# led_daughter.net
KiCad netlist of a schematic drawn in EAGLE
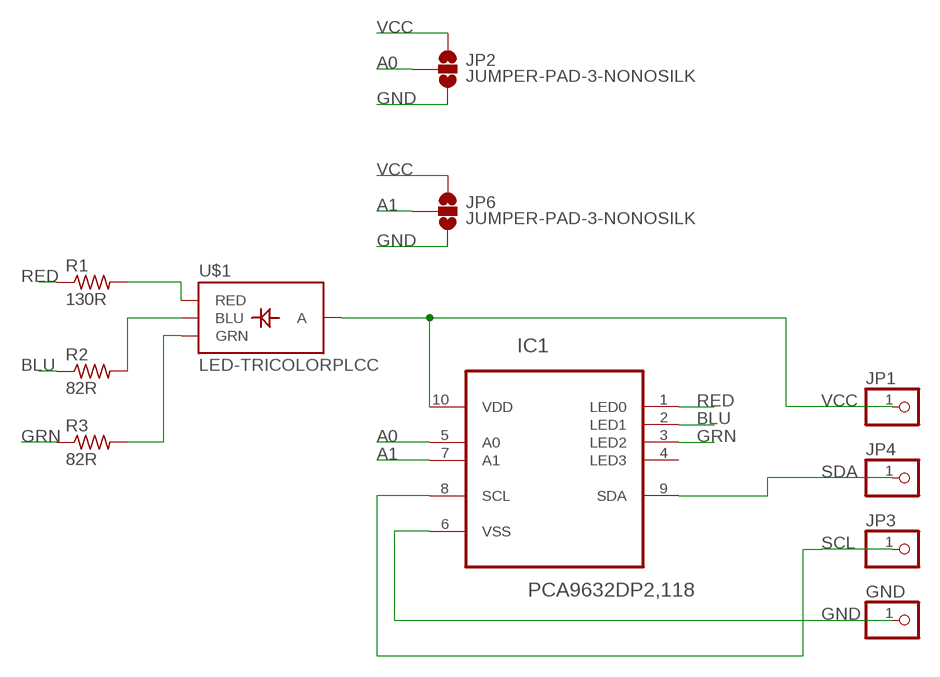
[diagram p0: schematic, sheet 1]

(export (version "E")
  (design (tool "Eeschema 10.0.6"))
  (components
    (comp (ref "GND")
      (value "PINHD-1X1CB")
      (footprint "eagle-import:1X01-CLEANBIG")
      (libsource (lib "eagle-import") (part "PINHD-1X1CB"))
    )
    (comp (ref "IC1")
      (value "PCA9632DP2,118")
      (footprint "eagle-import:SOP50P490X110-10N")
      (libsource (lib "eagle-import") (part "PCA9632DP2,118"))
    )
    (comp (ref "JP1")
      (value "PINHD-1X1CB")
      (footprint "eagle-import:1X01-CLEANBIG")
      (libsource (lib "eagle-import") (part "PINHD-1X1CB"))
    )
    (comp (ref "JP2")
      (value "JUMPER-PAD-3-NONOSILK")
      (footprint "eagle-import:PAD-JUMPER-3-NO_NO_SILK")
      (libsource (lib "eagle-import") (part "JUMPER-PAD-3-NONOSILK"))
    )
    (comp (ref "JP3")
      (value "PINHD-1X1CB")
      (footprint "eagle-import:1X01-CLEANBIG")
      (libsource (lib "eagle-import") (part "PINHD-1X1CB"))
    )
    (comp (ref "JP4")
      (value "PINHD-1X1CB")
      (footprint "eagle-import:1X01-CLEANBIG")
      (libsource (lib "eagle-import") (part "PINHD-1X1CB"))
    )
    (comp (ref "JP6")
      (value "JUMPER-PAD-3-NONOSILK")
      (footprint "eagle-import:PAD-JUMPER-3-NO_NO_SILK")
      (libsource (lib "eagle-import") (part "JUMPER-PAD-3-NONOSILK"))
    )
    (comp (ref "R1")
      (value "130R")
      (footprint "eagle-import:R0603")
      (libsource (lib "eagle-import") (part "R-US_R0603"))
    )
    (comp (ref "R2")
      (value "82R")
      (footprint "eagle-import:R0603")
      (libsource (lib "eagle-import") (part "R-US_R0603"))
    )
    (comp (ref "R3")
      (value "82R")
      (footprint "eagle-import:R0603")
      (libsource (lib "eagle-import") (part "R-US_R0603"))
    )
    (comp (ref "U$1")
      (value "LED-TRICOLORPLCC")
      (footprint "eagle-import:LED-TRICOLOR-PLCC")
      (libsource (lib "eagle-import") (part "LED-TRICOLORPLCC"))
    )
  )
  (nets
    (net (code "1") (name "/A0") (class "Default")
      (node (ref "IC1") (pin "5") (pinfunction "A0_5") (pintype "input"))
      (node (ref "JP2") (pin "2") (pinfunction "2_2") (pintype "passive"))
    )
    (net (code "2") (name "/A1") (class "Default")
      (node (ref "IC1") (pin "7") (pinfunction "A1_7") (pintype "input"))
      (node (ref "JP6") (pin "2") (pinfunction "2_2") (pintype "passive"))
    )
    (net (code "3") (name "/BLU") (class "Default")
      (node (ref "IC1") (pin "2") (pinfunction "LED1_2") (pintype "output"))
      (node (ref "R2") (pin "1") (pinfunction "1_1") (pintype "passive"))
    )
    (net (code "4") (name "/GND") (class "Default")
      (node (ref "GND") (pin "1") (pinfunction "1_1") (pintype "passive"))
      (node (ref "IC1") (pin "6") (pinfunction "VSS_6") (pintype "power_in"))
      (node (ref "JP2") (pin "3") (pinfunction "3_3") (pintype "passive"))
      (node (ref "JP6") (pin "3") (pinfunction "3_3") (pintype "passive"))
    )
    (net (code "5") (name "/GRN") (class "Default")
      (node (ref "IC1") (pin "3") (pinfunction "LED2_3") (pintype "output"))
      (node (ref "R3") (pin "1") (pinfunction "1_1") (pintype "passive"))
    )
    (net (code "6") (name "/RED") (class "Default")
      (node (ref "IC1") (pin "1") (pinfunction "LED0_1") (pintype "output"))
      (node (ref "R1") (pin "1") (pinfunction "1_1") (pintype "passive"))
    )
    (net (code "7") (name "/SCL") (class "Default")
      (node (ref "IC1") (pin "8") (pinfunction "SCL_8") (pintype "input"))
      (node (ref "JP3") (pin "1") (pinfunction "1_1") (pintype "passive"))
    )
    (net (code "8") (name "/SDA") (class "Default")
      (node (ref "IC1") (pin "9") (pinfunction "SDA_9") (pintype "bidirectional"))
      (node (ref "JP4") (pin "1") (pinfunction "1_1") (pintype "passive"))
    )
    (net (code "9") (name "/VCC") (class "Default")
      (node (ref "IC1") (pin "10") (pinfunction "VDD_10") (pintype "power_in"))
      (node (ref "JP1") (pin "1") (pinfunction "1_1") (pintype "passive"))
      (node (ref "JP2") (pin "1") (pinfunction "1_1") (pintype "passive"))
      (node (ref "JP6") (pin "1") (pinfunction "1_1") (pintype "passive"))
      (node (ref "U$1") (pin "PAD1") (pinfunction "A_PAD1") (pintype "bidirectional"))
    )
    (net (code "10") (name "Net-(U$1-BLU)") (class "Default")
      (node (ref "R2") (pin "2") (pinfunction "2_2") (pintype "passive"))
      (node (ref "U$1") (pin "PAD2") (pinfunction "BLU_PAD2") (pintype "bidirectional"))
    )
    (net (code "11") (name "Net-(U$1-GRN)") (class "Default")
      (node (ref "R3") (pin "2") (pinfunction "2_2") (pintype "passive"))
      (node (ref "U$1") (pin "PAD3") (pinfunction "GRN_PAD3") (pintype "bidirectional"))
    )
    (net (code "12") (name "Net-(U$1-RED)") (class "Default")
      (node (ref "R1") (pin "2") (pinfunction "2_2") (pintype "passive"))
      (node (ref "U$1") (pin "PAD4") (pinfunction "RED_PAD4") (pintype "bidirectional"))
    )
    (net (code "13") (name "unconnected-(IC1-LED3-Pad4)") (class "Default")
      (node (ref "IC1") (pin "4") (pinfunction "LED3_4") (pintype "output"))
    )
  )
)
